# Push_Button.net
KiCad netlist of a schematic drawn in Altium Designer
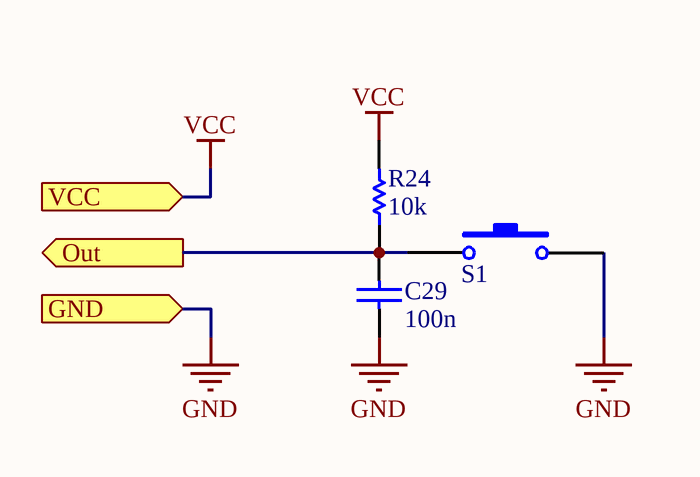
[diagram p0: Push_Button.SchDoc]

(export (version "E")
  (design (tool "Eeschema 10.0.6"))
  (components
    (comp (ref "C29")
      (value "100n")
      (footprint "CS-0603")
      (fields
        (field (name "TOLERANCE") "10%")
        (field (name "VOLTAGE") "16V")
        (field (name "Comment") "CS - CAPACITOR")
      )
      (libsource (lib "CHINOOK_LIBRARY") (part "CS - CAPACITOR"))
    )
    (comp (ref "R24")
      (value "10k")
      (footprint "RS-0603")
      (fields
        (field (name "TOLERANCE") "RES TOL")
        (field (name "POWER") "RES POWER")
        (field (name "Comment") "RS - RESISTOR")
      )
      (libsource (lib "CHINOOK_LIBRARY") (part "RS - RESISTOR"))
    )
    (comp (ref "S1")
      (value "SW - Tactile Switch")
      (footprint "SW-FSMRA")
      (libsource (lib "CHINOOK_LIBRARY") (part "SW - Tactile Switch"))
    )
  )
  (nets
    (net (code "1") (name "/Out") (class "Default")
      (node (ref "C29") (pin "2") (pinfunction "2_2") (pintype "passive"))
      (node (ref "R24") (pin "1") (pinfunction "1_1") (pintype "passive"))
      (node (ref "S1") (pin "1") (pinfunction "1_1") (pintype "passive"))
    )
    (net (code "2") (name "GND") (class "Default")
      (node (ref "C29") (pin "1") (pinfunction "1_1") (pintype "passive"))
      (node (ref "S1") (pin "2") (pinfunction "2_2") (pintype "passive"))
    )
    (net (code "3") (name "VCC") (class "Default")
      (node (ref "R24") (pin "2") (pinfunction "2_2") (pintype "passive"))
    )
  )
)
